# RFTP2917.net
KiCad netlist of a schematic drawn in Altium Designer
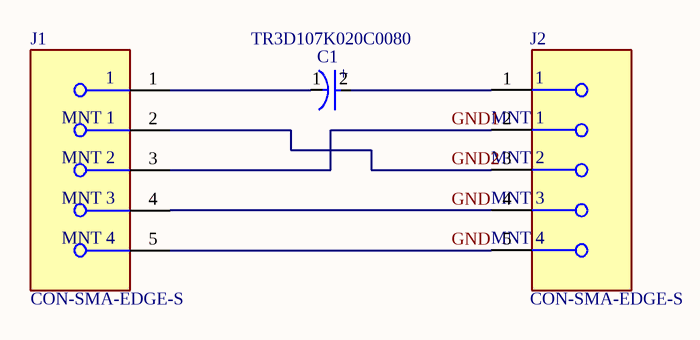
[diagram p0: RFTP2917.SchDoc]

(export (version "E")
  (design (tool "Eeschema 10.0.6"))
  (components
    (comp (ref "C1")
      (value "TR3D107K020C0080")
      (footprint "FP-TR3D-MFG")
      (fields (field (name "TOLERANCE") "10%"))
      (libsource (lib "Altium Content Vault") (part "203bc49f2ac43e59fd269a8c329ed05"))
    )
    (comp (ref "J1")
      (value "CON-SMA-EDGE-S")
      (footprint "FP-CON-SMA-EDGE-S-MFG")
      (description "CONN SMA JACK STR EDGE MNT")
      (fields
        (field (name "OCTOPART") "https://octopart.com/con-sma-edge-s-rf+solutions-70967450")
        (field (name "MANUFACTURER") "RF Solutions Ltd.")
      )
      (libsource (lib "Altium Content Vault") (part "a163d97a771fcdd2fd1f1a9264c171f"))
    )
    (comp (ref "J2")
      (value "CON-SMA-EDGE-S")
      (footprint "FP-CON-SMA-EDGE-S-MFG")
      (description "CONN SMA JACK STR EDGE MNT")
      (fields
        (field (name "OCTOPART") "https://octopart.com/con-sma-edge-s-rf+solutions-70967450")
        (field (name "MANUFACTURER") "RF Solutions Ltd.")
      )
      (libsource (lib "") (part "a163d97a771fcdd2fd1f1a9264c171f_1"))
    )
  )
  (nets
    (net (code "1") (name "/GND") (class "Default")
      (node (ref "J1") (pin "4") (pinfunction "MNT_3_4") (pintype "passive"))
      (node (ref "J1") (pin "5") (pinfunction "MNT_4_5") (pintype "passive"))
      (node (ref "J2") (pin "4") (pinfunction "MNT_3_4") (pintype "passive"))
      (node (ref "J2") (pin "5") (pinfunction "MNT_4_5") (pintype "passive"))
    )
    (net (code "2") (name "/GND1") (class "Default")
      (node (ref "J1") (pin "3") (pinfunction "MNT_2_3") (pintype "passive"))
      (node (ref "J2") (pin "2") (pinfunction "MNT_1_2") (pintype "passive"))
    )
    (net (code "3") (name "/GND2") (class "Default")
      (node (ref "J1") (pin "2") (pinfunction "MNT_1_2") (pintype "passive"))
      (node (ref "J2") (pin "3") (pinfunction "MNT_2_3") (pintype "passive"))
    )
    (net (code "4") (name "Net-(C1-A)") (class "Default")
      (node (ref "C1") (pin "2") (pinfunction "A_2") (pintype "passive"))
      (node (ref "J2") (pin "1") (pinfunction "1_1") (pintype "passive"))
    )
    (net (code "5") (name "Net-(C1-C)") (class "Default")
      (node (ref "C1") (pin "1") (pinfunction "C_1") (pintype "passive"))
      (node (ref "J1") (pin "1") (pinfunction "1_1") (pintype "passive"))
    )
  )
)
